# LPF.net
KiCad netlist of a schematic drawn in EAGLE
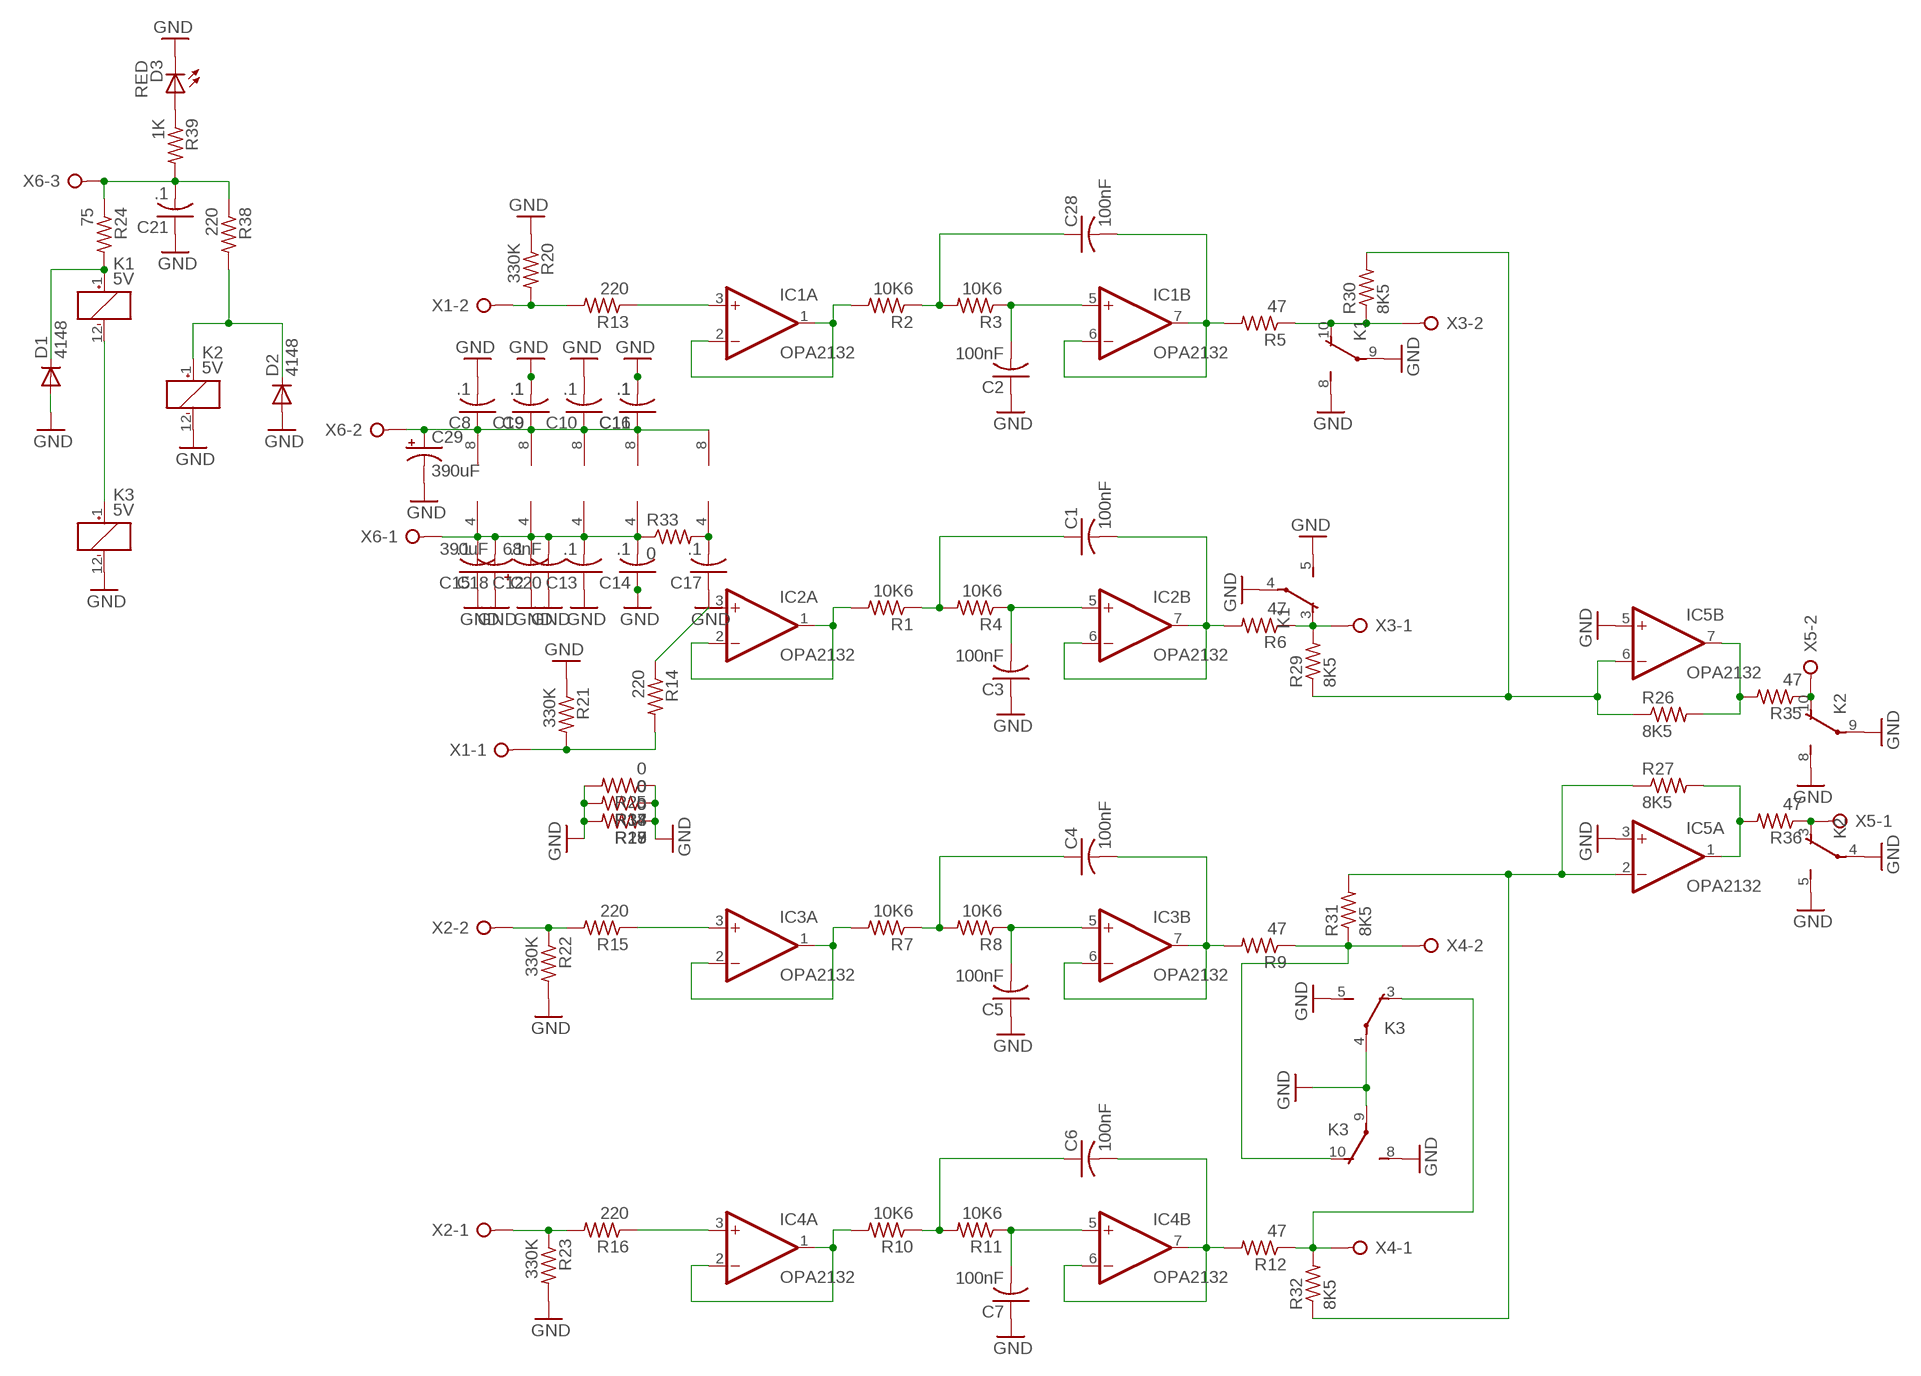
[diagram p0: schematic, sheet 1]

(export (version "E")
  (design (tool "Eeschema 10.0.6"))
  (components
    (comp (ref "C1")
      (value "100nF")
      (footprint "eagle-import:C050-075X075")
      (libsource (lib "eagle-import") (part "C-US050-075X075"))
    )
    (comp (ref "C2")
      (value "100nF")
      (footprint "eagle-import:C050-075X075")
      (libsource (lib "eagle-import") (part "C-US050-075X075"))
    )
    (comp (ref "C3")
      (value "100nF")
      (footprint "eagle-import:C050-075X075")
      (libsource (lib "eagle-import") (part "C-US050-075X075"))
    )
    (comp (ref "C4")
      (value "100nF")
      (footprint "eagle-import:C050-075X075")
      (libsource (lib "eagle-import") (part "C-US050-075X075"))
    )
    (comp (ref "C5")
      (value "100nF")
      (footprint "eagle-import:C050-075X075")
      (libsource (lib "eagle-import") (part "C-US050-075X075"))
    )
    (comp (ref "C6")
      (value "100nF")
      (footprint "eagle-import:C050-075X075")
      (libsource (lib "eagle-import") (part "C-US050-075X075"))
    )
    (comp (ref "C7")
      (value "100nF")
      (footprint "eagle-import:C050-075X075")
      (libsource (lib "eagle-import") (part "C-US050-075X075"))
    )
    (comp (ref "C8")
      (value ".1")
      (footprint "eagle-import:C4532")
      (libsource (lib "eagle-import") (part "C-USC4532"))
    )
    (comp (ref "C9")
      (value ".1")
      (footprint "eagle-import:C4532")
      (libsource (lib "eagle-import") (part "C-USC4532"))
    )
    (comp (ref "C10")
      (value ".1")
      (footprint "eagle-import:C4532")
      (libsource (lib "eagle-import") (part "C-USC4532"))
    )
    (comp (ref "C11")
      (value ".1")
      (footprint "eagle-import:C4532")
      (libsource (lib "eagle-import") (part "C-USC4532"))
    )
    (comp (ref "C12")
      (value ".1")
      (footprint "eagle-import:C4532")
      (libsource (lib "eagle-import") (part "C-USC4532"))
    )
    (comp (ref "C13")
      (value ".1")
      (footprint "eagle-import:C4532")
      (libsource (lib "eagle-import") (part "C-USC4532"))
    )
    (comp (ref "C14")
      (value ".1")
      (footprint "eagle-import:C4532")
      (libsource (lib "eagle-import") (part "C-USC4532"))
    )
    (comp (ref "C15")
      (value ".1")
      (footprint "eagle-import:C4532")
      (libsource (lib "eagle-import") (part "C-USC4532"))
    )
    (comp (ref "C16")
      (value ".1")
      (footprint "eagle-import:C4532")
      (libsource (lib "eagle-import") (part "C-USC4532"))
    )
    (comp (ref "C17")
      (value ".1")
      (footprint "eagle-import:C4532")
      (libsource (lib "eagle-import") (part "C-USC4532"))
    )
    (comp (ref "C18")
      (value "390uF")
      (footprint "eagle-import:E5-13")
      (libsource (lib "eagle-import") (part "CPOL-USE5-13"))
    )
    (comp (ref "C19")
      (value ".1")
      (footprint "eagle-import:C4532")
      (libsource (lib "eagle-import") (part "C-USC4532"))
    )
    (comp (ref "C20")
      (value "68nF")
      (footprint "eagle-import:C075-042X103")
      (libsource (lib "eagle-import") (part "C-US075-042X103"))
    )
    (comp (ref "C21")
      (value ".1")
      (footprint "eagle-import:C4532")
      (libsource (lib "eagle-import") (part "C-USC4532"))
    )
    (comp (ref "C28")
      (value "100nF")
      (footprint "eagle-import:C050-075X075")
      (libsource (lib "eagle-import") (part "C-US050-075X075"))
    )
    (comp (ref "C29")
      (value "390uF")
      (footprint "eagle-import:E5-13")
      (libsource (lib "eagle-import") (part "CPOL-USE5-13"))
    )
    (comp (ref "D1")
      (value "4148")
      (footprint "eagle-import:DO35-7")
      (libsource (lib "eagle-import") (part "1N4148DO35-7"))
    )
    (comp (ref "D2")
      (value "4148")
      (footprint "eagle-import:DO35-7")
      (libsource (lib "eagle-import") (part "1N4148DO35-7"))
    )
    (comp (ref "D3")
      (value "RED")
      (footprint "eagle-import:SFH482")
      (libsource (lib "eagle-import") (part "SFH482"))
    )
    (comp (ref "IC1")
      (value "OPA2132")
      (footprint "eagle-import:DIL08")
      (libsource (lib "eagle-import") (part "1458NLM"))
    )
    (comp (ref "IC2")
      (value "OPA2132")
      (footprint "eagle-import:DIL08")
      (libsource (lib "eagle-import") (part "1458NLM"))
    )
    (comp (ref "IC3")
      (value "OPA2132")
      (footprint "eagle-import:DIL08")
      (libsource (lib "eagle-import") (part "1458NLM"))
    )
    (comp (ref "IC4")
      (value "OPA2132")
      (footprint "eagle-import:DIL08")
      (libsource (lib "eagle-import") (part "1458NLM"))
    )
    (comp (ref "IC5")
      (value "OPA2132")
      (footprint "eagle-import:DIL08")
      (libsource (lib "eagle-import") (part "1458NLM"))
    )
    (comp (ref "K1")
      (value "5V")
      (footprint "eagle-import:TX2")
      (fields
        (field (name "MF") "AROMAT/ MATSUSHITA")
        (field (name "MPN") "TX2-12V")
        (field (name "MF_1") "AROMAT/ MATSUSHITA")
        (field (name "MPN_1") "TX2-12V")
        (field (name "OC_FARNELL") "1200952")
        (field (name "OC_NEWARK") "67K1295")
      )
      (libsource (lib "eagle-import") (part "TX2?-12V"))
    )
    (comp (ref "K2")
      (value "5V")
      (footprint "eagle-import:TX2")
      (fields
        (field (name "MF") "AROMAT/ MATSUSHITA")
        (field (name "MPN") "TX2-12V")
        (field (name "MF_1") "AROMAT/ MATSUSHITA")
        (field (name "MPN_1") "TX2-12V")
        (field (name "OC_FARNELL") "1200952")
        (field (name "OC_NEWARK") "67K1295")
      )
      (libsource (lib "eagle-import") (part "TX2?-12V"))
    )
    (comp (ref "K3")
      (value "5V")
      (footprint "eagle-import:TX2")
      (fields
        (field (name "MF") "AROMAT/ MATSUSHITA")
        (field (name "MPN") "TX2-12V")
        (field (name "MF_1") "AROMAT/ MATSUSHITA")
        (field (name "MPN_1") "TX2-12V")
        (field (name "OC_FARNELL") "1200952")
        (field (name "OC_NEWARK") "67K1295")
      )
      (libsource (lib "eagle-import") (part "TX2?-12V"))
    )
    (comp (ref "R1")
      (value "10K6")
      (footprint "eagle-import:0207_10")
      (libsource (lib "eagle-import") (part "R-US_0207/10"))
    )
    (comp (ref "R2")
      (value "10K6")
      (footprint "eagle-import:0207_10")
      (libsource (lib "eagle-import") (part "R-US_0207/10"))
    )
    (comp (ref "R3")
      (value "10K6")
      (footprint "eagle-import:0207_10")
      (libsource (lib "eagle-import") (part "R-US_0207/10"))
    )
    (comp (ref "R4")
      (value "10K6")
      (footprint "eagle-import:0207_10")
      (libsource (lib "eagle-import") (part "R-US_0207/10"))
    )
    (comp (ref "R5")
      (value "47")
      (footprint "eagle-import:0207_12")
      (libsource (lib "eagle-import") (part "R-US_0207/12"))
    )
    (comp (ref "R6")
      (value "47")
      (footprint "eagle-import:0207_12")
      (libsource (lib "eagle-import") (part "R-US_0207/12"))
    )
    (comp (ref "R7")
      (value "10K6")
      (footprint "eagle-import:0207_10")
      (libsource (lib "eagle-import") (part "R-US_0207/10"))
    )
    (comp (ref "R8")
      (value "10K6")
      (footprint "eagle-import:0207_10")
      (libsource (lib "eagle-import") (part "R-US_0207/10"))
    )
    (comp (ref "R9")
      (value "47")
      (footprint "eagle-import:0207_12")
      (libsource (lib "eagle-import") (part "R-US_0207/12"))
    )
    (comp (ref "R10")
      (value "10K6")
      (footprint "eagle-import:0207_10")
      (libsource (lib "eagle-import") (part "R-US_0207/10"))
    )
    (comp (ref "R11")
      (value "10K6")
      (footprint "eagle-import:0207_10")
      (libsource (lib "eagle-import") (part "R-US_0207/10"))
    )
    (comp (ref "R12")
      (value "47")
      (footprint "eagle-import:0207_10")
      (libsource (lib "eagle-import") (part "R-US_0207/10"))
    )
    (comp (ref "R13")
      (value "220")
      (footprint "eagle-import:0207_10")
      (libsource (lib "eagle-import") (part "R-US_0207/10"))
    )
    (comp (ref "R14")
      (value "220")
      (footprint "eagle-import:0207_10")
      (libsource (lib "eagle-import") (part "R-US_0207/10"))
    )
    (comp (ref "R15")
      (value "220")
      (footprint "eagle-import:0207_10")
      (libsource (lib "eagle-import") (part "R-US_0207/10"))
    )
    (comp (ref "R16")
      (value "220")
      (footprint "eagle-import:0207_10")
      (libsource (lib "eagle-import") (part "R-US_0207/10"))
    )
    (comp (ref "R17")
      (value "0")
      (footprint "eagle-import:0204_7")
      (libsource (lib "eagle-import") (part "R-US_0204/7"))
    )
    (comp (ref "R18")
      (value "0")
      (footprint "eagle-import:0204_7")
      (libsource (lib "eagle-import") (part "R-US_0204/7"))
    )
    (comp (ref "R19")
      (value "0")
      (footprint "eagle-import:0204_7")
      (libsource (lib "eagle-import") (part "R-US_0204/7"))
    )
    (comp (ref "R20")
      (value "330K")
      (footprint "eagle-import:R1210")
      (libsource (lib "eagle-import") (part "R-US_R1210"))
    )
    (comp (ref "R21")
      (value "330K")
      (footprint "eagle-import:R1210")
      (libsource (lib "eagle-import") (part "R-US_R1210"))
    )
    (comp (ref "R22")
      (value "330K")
      (footprint "eagle-import:R1210")
      (libsource (lib "eagle-import") (part "R-US_R1210"))
    )
    (comp (ref "R23")
      (value "330K")
      (footprint "eagle-import:R1210")
      (libsource (lib "eagle-import") (part "R-US_R1210"))
    )
    (comp (ref "R24")
      (value "75")
      (footprint "eagle-import:0207_10")
      (libsource (lib "eagle-import") (part "R-US_0207/10"))
    )
    (comp (ref "R25")
      (value "0")
      (footprint "eagle-import:0204_7")
      (libsource (lib "eagle-import") (part "R-US_0204/7"))
    )
    (comp (ref "R26")
      (value "8K5")
      (footprint "eagle-import:R1210")
      (libsource (lib "eagle-import") (part "R-US_R1210"))
    )
    (comp (ref "R27")
      (value "8K5")
      (footprint "eagle-import:R1210")
      (libsource (lib "eagle-import") (part "R-US_R1210"))
    )
    (comp (ref "R28")
      (value "0")
      (footprint "eagle-import:0204_7")
      (libsource (lib "eagle-import") (part "R-US_0204/7"))
    )
    (comp (ref "R29")
      (value "8K5")
      (footprint "eagle-import:R1210")
      (libsource (lib "eagle-import") (part "R-US_R1210"))
    )
    (comp (ref "R30")
      (value "8K5")
      (footprint "eagle-import:R1210")
      (libsource (lib "eagle-import") (part "R-US_R1210"))
    )
    (comp (ref "R31")
      (value "8K5")
      (footprint "eagle-import:R1210")
      (libsource (lib "eagle-import") (part "R-US_R1210"))
    )
    (comp (ref "R32")
      (value "8K5")
      (footprint "eagle-import:R1210")
      (libsource (lib "eagle-import") (part "R-US_R1210"))
    )
    (comp (ref "R33")
      (value "0")
      (footprint "eagle-import:0207_12")
      (libsource (lib "eagle-import") (part "R-US_0207/12"))
    )
    (comp (ref "R34")
      (value "0")
      (footprint "eagle-import:0204_7")
      (libsource (lib "eagle-import") (part "R-US_0204/7"))
    )
    (comp (ref "R35")
      (value "47")
      (footprint "eagle-import:0207_10")
      (libsource (lib "eagle-import") (part "R-US_0207/10"))
    )
    (comp (ref "R36")
      (value "47")
      (footprint "eagle-import:0207_10")
      (libsource (lib "eagle-import") (part "R-US_0207/10"))
    )
    (comp (ref "R37")
      (value "0")
      (footprint "eagle-import:0207_10")
      (libsource (lib "eagle-import") (part "R-US_0207/10"))
    )
    (comp (ref "R38")
      (value "220")
      (footprint "eagle-import:0309_12")
      (libsource (lib "eagle-import") (part "R-US_0309/12"))
    )
    (comp (ref "R39")
      (value "1K")
      (footprint "eagle-import:0207_10")
      (libsource (lib "eagle-import") (part "R-US_0207/10"))
    )
    (comp (ref "X1")
      (value "W237-02P")
      (footprint "eagle-import:W237-132")
      (libsource (lib "eagle-import") (part "W237-02P"))
    )
    (comp (ref "X2")
      (value "W237-02P")
      (footprint "eagle-import:W237-132")
      (libsource (lib "eagle-import") (part "W237-02P"))
    )
    (comp (ref "X3")
      (value "W237-02P")
      (footprint "eagle-import:W237-132")
      (fields (field (name "OC_FARNELL") "unknown") (field (name "OC_NEWARK") "unknown"))
      (libsource (lib "eagle-import") (part "W237-02P"))
    )
    (comp (ref "X4")
      (value "W237-02P")
      (footprint "eagle-import:W237-132")
      (fields (field (name "OC_FARNELL") "unknown") (field (name "OC_NEWARK") "unknown"))
      (libsource (lib "eagle-import") (part "W237-02P"))
    )
    (comp (ref "X5")
      (value "W237-02P")
      (footprint "eagle-import:W237-132")
      (fields (field (name "OC_FARNELL") "unknown") (field (name "OC_NEWARK") "unknown"))
      (libsource (lib "eagle-import") (part "W237-02P"))
    )
    (comp (ref "X6")
      (value "W237-3E")
      (footprint "eagle-import:W237-3E")
      (libsource (lib "eagle-import") (part "W237-3E"))
    )
  )
  (nets
    (net (code "1") (name "GND") (class "Default")
      (node (ref "C10") (pin "2") (pinfunction "2_2") (pintype "passive"))
      (node (ref "C11") (pin "2") (pinfunction "2_2") (pintype "passive"))
      (node (ref "C12") (pin "1") (pinfunction "1_1") (pintype "passive"))
      (node (ref "C13") (pin "1") (pinfunction "1_1") (pintype "passive"))
      (node (ref "C14") (pin "1") (pinfunction "1_1") (pintype "passive"))
      (node (ref "C15") (pin "1") (pinfunction "1_1") (pintype "passive"))
      (node (ref "C16") (pin "2") (pinfunction "2_2") (pintype "passive"))
      (node (ref "C17") (pin "1") (pinfunction "1_1") (pintype "passive"))
      (node (ref "C18") (pin "+") (pinfunction "+_+") (pintype "passive"))
      (node (ref "C19") (pin "2") (pinfunction "2_2") (pintype "passive"))
      (node (ref "C2") (pin "1") (pinfunction "1_1") (pintype "passive"))
      (node (ref "C20") (pin "1") (pinfunction "1_1") (pintype "passive"))
      (node (ref "C21") (pin "1") (pinfunction "1_1") (pintype "passive"))
      (node (ref "C29") (pin "-") (pinfunction "-_-") (pintype "passive"))
      (node (ref "C3") (pin "1") (pinfunction "1_1") (pintype "passive"))
      (node (ref "C5") (pin "1") (pinfunction "1_1") (pintype "passive"))
      (node (ref "C7") (pin "1") (pinfunction "1_1") (pintype "passive"))
      (node (ref "C8") (pin "2") (pinfunction "2_2") (pintype "passive"))
      (node (ref "C9") (pin "2") (pinfunction "2_2") (pintype "passive"))
      (node (ref "D1") (pin "A") (pinfunction "A_A") (pintype "passive"))
      (node (ref "D2") (pin "A") (pinfunction "A_A") (pintype "passive"))
      (node (ref "D3") (pin "K") (pinfunction "C_K") (pintype "passive"))
      (node (ref "IC5") (pin "3") (pinfunction "+IN_3") (pintype "input"))
      (node (ref "IC5") (pin "5") (pinfunction "+IN_5") (pintype "input"))
      (node (ref "K1") (pin "4") (pinfunction "P_4") (pintype "passive"))
      (node (ref "K1") (pin "5") (pinfunction "S_5") (pintype "passive"))
      (node (ref "K1") (pin "8") (pinfunction "S_8") (pintype "passive"))
      (node (ref "K1") (pin "9") (pinfunction "P_9") (pintype "passive"))
      (node (ref "K2") (pin "12") (pinfunction "-_12") (pintype "passive"))
      (node (ref "K2") (pin "4") (pinfunction "P_4") (pintype "passive"))
      (node (ref "K2") (pin "5") (pinfunction "S_5") (pintype "passive"))
      (node (ref "K2") (pin "8") (pinfunction "S_8") (pintype "passive"))
      (node (ref "K2") (pin "9") (pinfunction "P_9") (pintype "passive"))
      (node (ref "K3") (pin "12") (pinfunction "-_12") (pintype "passive"))
      (node (ref "K3") (pin "4") (pinfunction "P_4") (pintype "passive"))
      (node (ref "K3") (pin "5") (pinfunction "S_5") (pintype "passive"))
      (node (ref "K3") (pin "8") (pinfunction "S_8") (pintype "passive"))
      (node (ref "K3") (pin "9") (pinfunction "P_9") (pintype "passive"))
      (node (ref "R17") (pin "1") (pinfunction "1_1") (pintype "passive"))
      (node (ref "R17") (pin "2") (pinfunction "2_2") (pintype "passive"))
      (node (ref "R18") (pin "1") (pinfunction "1_1") (pintype "passive"))
      (node (ref "R18") (pin "2") (pinfunction "2_2") (pintype "passive"))
      (node (ref "R19") (pin "1") (pinfunction "1_1") (pintype "passive"))
      (node (ref "R19") (pin "2") (pinfunction "2_2") (pintype "passive"))
      (node (ref "R20") (pin "1") (pinfunction "1_1") (pintype "passive"))
      (node (ref "R21") (pin "1") (pinfunction "1_1") (pintype "passive"))
      (node (ref "R22") (pin "2") (pinfunction "2_2") (pintype "passive"))
      (node (ref "R23") (pin "2") (pinfunction "2_2") (pintype "passive"))
      (node (ref "R25") (pin "1") (pinfunction "1_1") (pintype "passive"))
      (node (ref "R25") (pin "2") (pinfunction "2_2") (pintype "passive"))
      (node (ref "R28") (pin "1") (pinfunction "1_1") (pintype "passive"))
      (node (ref "R28") (pin "2") (pinfunction "2_2") (pintype "passive"))
      (node (ref "R34") (pin "1") (pinfunction "1_1") (pintype "passive"))
      (node (ref "R34") (pin "2") (pinfunction "2_2") (pintype "passive"))
      (node (ref "R37") (pin "1") (pinfunction "1_1") (pintype "passive"))
      (node (ref "R37") (pin "2") (pinfunction "2_2") (pintype "passive"))
    )
    (net (code "2") (name "Net-(C1-Pad1)") (class "Default")
      (node (ref "C1") (pin "1") (pinfunction "1_1") (pintype "passive"))
      (node (ref "R1") (pin "1") (pinfunction "1_1") (pintype "passive"))
      (node (ref "R4") (pin "2") (pinfunction "2_2") (pintype "passive"))
    )
    (net (code "3") (name "Net-(C4-Pad1)") (class "Default")
      (node (ref "C4") (pin "1") (pinfunction "1_1") (pintype "passive"))
      (node (ref "R7") (pin "1") (pinfunction "1_1") (pintype "passive"))
      (node (ref "R8") (pin "2") (pinfunction "2_2") (pintype "passive"))
    )
    (net (code "4") (name "Net-(C6-Pad1)") (class "Default")
      (node (ref "C6") (pin "1") (pinfunction "1_1") (pintype "passive"))
      (node (ref "R10") (pin "1") (pinfunction "1_1") (pintype "passive"))
      (node (ref "R11") (pin "2") (pinfunction "2_2") (pintype "passive"))
    )
    (net (code "5") (name "Net-(C28-Pad1)") (class "Default")
      (node (ref "C28") (pin "1") (pinfunction "1_1") (pintype "passive"))
      (node (ref "R2") (pin "1") (pinfunction "1_1") (pintype "passive"))
      (node (ref "R3") (pin "2") (pinfunction "2_2") (pintype "passive"))
    )
    (net (code "6") (name "Net-(D3-PadA)") (class "Default")
      (node (ref "D3") (pin "A") (pinfunction "A_A") (pintype "passive"))
      (node (ref "R39") (pin "1") (pinfunction "1_1") (pintype "passive"))
    )
    (net (code "7") (name "Net-(IC1A-+IN)") (class "Default")
      (node (ref "IC1") (pin "3") (pinfunction "+IN_3") (pintype "input"))
      (node (ref "R13") (pin "1") (pinfunction "1_1") (pintype "passive"))
    )
    (net (code "8") (name "Net-(IC1A--IN)") (class "Default")
      (node (ref "IC1") (pin "1") (pinfunction "OUT_1") (pintype "output"))
      (node (ref "IC1") (pin "2") (pinfunction "-IN_2") (pintype "input"))
      (node (ref "R2") (pin "2") (pinfunction "2_2") (pintype "passive"))
    )
    (net (code "9") (name "Net-(IC1B-+IN)") (class "Default")
      (node (ref "C2") (pin "2") (pinfunction "2_2") (pintype "passive"))
      (node (ref "IC1") (pin "5") (pinfunction "+IN_5") (pintype "input"))
      (node (ref "R3") (pin "1") (pinfunction "1_1") (pintype "passive"))
    )
    (net (code "10") (name "Net-(IC1B--IN)") (class "Default")
      (node (ref "C28") (pin "2") (pinfunction "2_2") (pintype "passive"))
      (node (ref "IC1") (pin "6") (pinfunction "-IN_6") (pintype "input"))
      (node (ref "IC1") (pin "7") (pinfunction "OUT_7") (pintype "output"))
      (node (ref "R5") (pin "2") (pinfunction "2_2") (pintype "passive"))
    )
    (net (code "11") (name "Net-(IC1C-V+)") (class "Default")
      (node (ref "C10") (pin "1") (pinfunction "1_1") (pintype "passive"))
      (node (ref "C11") (pin "1") (pinfunction "1_1") (pintype "passive"))
      (node (ref "C16") (pin "1") (pinfunction "1_1") (pintype "passive"))
      (node (ref "C19") (pin "1") (pinfunction "1_1") (pintype "passive"))
      (node (ref "C29") (pin "+") (pinfunction "+_+") (pintype "passive"))
      (node (ref "C8") (pin "1") (pinfunction "1_1") (pintype "passive"))
      (node (ref "C9") (pin "1") (pinfunction "1_1") (pintype "passive"))
      (node (ref "IC1") (pin "8") (pinfunction "V+_8") (pintype "power_in"))
      (node (ref "IC2") (pin "8") (pinfunction "V+_8") (pintype "power_in"))
      (node (ref "IC3") (pin "8") (pinfunction "V+_8") (pintype "power_in"))
      (node (ref "IC4") (pin "8") (pinfunction "V+_8") (pintype "power_in"))
      (node (ref "IC5") (pin "8") (pinfunction "V+_8") (pintype "power_in"))
      (node (ref "X6") (pin "2") (pinfunction "KL_2") (pintype "passive"))
    )
    (net (code "12") (name "Net-(IC1C-V-)") (class "Default")
      (node (ref "C12") (pin "2") (pinfunction "2_2") (pintype "passive"))
      (node (ref "C13") (pin "2") (pinfunction "2_2") (pintype "passive"))
      (node (ref "C14") (pin "2") (pinfunction "2_2") (pintype "passive"))
      (node (ref "C15") (pin "2") (pinfunction "2_2") (pintype "passive"))
      (node (ref "C18") (pin "-") (pinfunction "-_-") (pintype "passive"))
      (node (ref "C20") (pin "2") (pinfunction "2_2") (pintype "passive"))
      (node (ref "IC1") (pin "4") (pinfunction "V-_4") (pintype "power_in"))
      (node (ref "IC2") (pin "4") (pinfunction "V-_4") (pintype "power_in"))
      (node (ref "IC3") (pin "4") (pinfunction "V-_4") (pintype "power_in"))
      (node (ref "IC4") (pin "4") (pinfunction "V-_4") (pintype "power_in"))
      (node (ref "R33") (pin "1") (pinfunction "1_1") (pintype "passive"))
      (node (ref "X6") (pin "1") (pinfunction "KL_1") (pintype "passive"))
    )
    (net (code "13") (name "Net-(IC2A-+IN)") (class "Default")
      (node (ref "IC2") (pin "3") (pinfunction "+IN_3") (pintype "input"))
      (node (ref "R14") (pin "1") (pinfunction "1_1") (pintype "passive"))
    )
    (net (code "14") (name "Net-(IC2A--IN)") (class "Default")
      (node (ref "IC2") (pin "1") (pinfunction "OUT_1") (pintype "output"))
      (node (ref "IC2") (pin "2") (pinfunction "-IN_2") (pintype "input"))
      (node (ref "R1") (pin "2") (pinfunction "2_2") (pintype "passive"))
    )
    (net (code "15") (name "Net-(IC2B-+IN)") (class "Default")
      (node (ref "C3") (pin "2") (pinfunction "2_2") (pintype "passive"))
      (node (ref "IC2") (pin "5") (pinfunction "+IN_5") (pintype "input"))
      (node (ref "R4") (pin "1") (pinfunction "1_1") (pintype "passive"))
    )
    (net (code "16") (name "Net-(IC2B--IN)") (class "Default")
      (node (ref "C1") (pin "2") (pinfunction "2_2") (pintype "passive"))
      (node (ref "IC2") (pin "6") (pinfunction "-IN_6") (pintype "input"))
      (node (ref "IC2") (pin "7") (pinfunction "OUT_7") (pintype "output"))
      (node (ref "R6") (pin "2") (pinfunction "2_2") (pintype "passive"))
    )
    (net (code "17") (name "Net-(IC3A-+IN)") (class "Default")
      (node (ref "IC3") (pin "3") (pinfunction "+IN_3") (pintype "input"))
      (node (ref "R15") (pin "1") (pinfunction "1_1") (pintype "passive"))
    )
    (net (code "18") (name "Net-(IC3A--IN)") (class "Default")
      (node (ref "IC3") (pin "1") (pinfunction "OUT_1") (pintype "output"))
      (node (ref "IC3") (pin "2") (pinfunction "-IN_2") (pintype "input"))
      (node (ref "R7") (pin "2") (pinfunction "2_2") (pintype "passive"))
    )
    (net (code "19") (name "Net-(IC3B-+IN)") (class "Default")
      (node (ref "C5") (pin "2") (pinfunction "2_2") (pintype "passive"))
      (node (ref "IC3") (pin "5") (pinfunction "+IN_5") (pintype "input"))
      (node (ref "R8") (pin "1") (pinfunction "1_1") (pintype "passive"))
    )
    (net (code "20") (name "Net-(IC3B--IN)") (class "Default")
      (node (ref "C4") (pin "2") (pinfunction "2_2") (pintype "passive"))
      (node (ref "IC3") (pin "6") (pinfunction "-IN_6") (pintype "input"))
      (node (ref "IC3") (pin "7") (pinfunction "OUT_7") (pintype "output"))
      (node (ref "R9") (pin "2") (pinfunction "2_2") (pintype "passive"))
    )
    (net (code "21") (name "Net-(IC4A-+IN)") (class "Default")
      (node (ref "IC4") (pin "3") (pinfunction "+IN_3") (pintype "input"))
      (node (ref "R16") (pin "1") (pinfunction "1_1") (pintype "passive"))
    )
    (net (code "22") (name "Net-(IC4A--IN)") (class "Default")
      (node (ref "IC4") (pin "1") (pinfunction "OUT_1") (pintype "output"))
      (node (ref "IC4") (pin "2") (pinfunction "-IN_2") (pintype "input"))
      (node (ref "R10") (pin "2") (pinfunction "2_2") (pintype "passive"))
    )
    (net (code "23") (name "Net-(IC4B-+IN)") (class "Default")
      (node (ref "C7") (pin "2") (pinfunction "2_2") (pintype "passive"))
      (node (ref "IC4") (pin "5") (pinfunction "+IN_5") (pintype "input"))
      (node (ref "R11") (pin "1") (pinfunction "1_1") (pintype "passive"))
    )
    (net (code "24") (name "Net-(IC4B--IN)") (class "Default")
      (node (ref "C6") (pin "2") (pinfunction "2_2") (pintype "passive"))
      (node (ref "IC4") (pin "6") (pinfunction "-IN_6") (pintype "input"))
      (node (ref "IC4") (pin "7") (pinfunction "OUT_7") (pintype "output"))
      (node (ref "R12") (pin "2") (pinfunction "2_2") (pintype "passive"))
    )
    (net (code "25") (name "Net-(IC5A--IN)") (class "Default")
      (node (ref "IC5") (pin "2") (pinfunction "-IN_2") (pintype "input"))
      (node (ref "R27") (pin "1") (pinfunction "1_1") (pintype "passive"))
      (node (ref "R31") (pin "2") (pinfunction "2_2") (pintype "passive"))
      (node (ref "R32") (pin "1") (pinfunction "1_1") (pintype "passive"))
    )
    (net (code "26") (name "Net-(IC5A-OUT)") (class "Default")
      (node (ref "IC5") (pin "1") (pinfunction "OUT_1") (pintype "output"))
      (node (ref "R27") (pin "2") (pinfunction "2_2") (pintype "passive"))
      (node (ref "R36") (pin "2") (pinfunction "2_2") (pintype "passive"))
    )
    (net (code "27") (name "Net-(IC5B--IN)") (class "Default")
      (node (ref "IC5") (pin "6") (pinfunction "-IN_6") (pintype "input"))
      (node (ref "R26") (pin "1") (pinfunction "1_1") (pintype "passive"))
      (node (ref "R29") (pin "1") (pinfunction "1_1") (pintype "passive"))
      (node (ref "R30") (pin "2") (pinfunction "2_2") (pintype "passive"))
    )
    (net (code "28") (name "Net-(IC5B-OUT)") (class "Default")
      (node (ref "IC5") (pin "7") (pinfunction "OUT_7") (pintype "output"))
      (node (ref "R26") (pin "2") (pinfunction "2_2") (pintype "passive"))
      (node (ref "R35") (pin "2") (pinfunction "2_2") (pintype "passive"))
    )
    (net (code "29") (name "Net-(IC5C-V-)") (class "Default")
      (node (ref "C17") (pin "2") (pinfunction "2_2") (pintype "passive"))
      (node (ref "IC5") (pin "4") (pinfunction "V-_4") (pintype "power_in"))
      (node (ref "R33") (pin "2") (pinfunction "2_2") (pintype "passive"))
    )
    (net (code "30") (name "Net-(K1A-O)") (class "Default")
      (node (ref "K1") (pin "3") (pinfunction "O_3") (pintype "passive"))
      (node (ref "R29") (pin "2") (pinfunction "2_2") (pintype "passive"))
      (node (ref "R6") (pin "1") (pinfunction "1_1") (pintype "passive"))
      (node (ref "X3") (pin "1") (pinfunction "KL_1") (pintype "passive"))
    )
    (net (code "31") (name "Net-(K1B-O)") (class "Default")
      (node (ref "K1") (pin "10") (pinfunction "O_10") (pintype "passive"))
      (node (ref "R30") (pin "1") (pinfunction "1_1") (pintype "passive"))
      (node (ref "R5") (pin "1") (pinfunction "1_1") (pintype "passive"))
      (node (ref "X3") (pin "2") (pinfunction "KL_2") (pintype "passive"))
    )
    (net (code "32") (name "Net-(K1C-+)") (class "Default")
      (node (ref "D1") (pin "C") (pinfunction "C_C") (pintype "passive"))
      (node (ref "K1") (pin "1") (pinfunction "+_1") (pintype "passive"))
      (node (ref "R24") (pin "2") (pinfunction "2_2") (pintype "passive"))
    )
    (net (code "33") (name "Net-(K1C--)") (class "Default")
      (node (ref "K1") (pin "12") (pinfunction "-_12") (pintype "passive"))
      (node (ref "K3") (pin "1") (pinfunction "+_1") (pintype "passive"))
    )
    (net (code "34") (name "Net-(K2A-O)") (class "Default")
      (node (ref "K2") (pin "3") (pinfunction "O_3") (pintype "passive"))
      (node (ref "R36") (pin "1") (pinfunction "1_1") (pintype "passive"))
      (node (ref "X5") (pin "1") (pinfunction "KL_1") (pintype "passive"))
    )
    (net (code "35") (name "Net-(K2B-O)") (class "Default")
      (node (ref "K2") (pin "10") (pinfunction "O_10") (pintype "passive"))
      (node (ref "R35") (pin "1") (pinfunction "1_1") (pintype "passive"))
      (node (ref "X5") (pin "2") (pinfunction "KL_2") (pintype "passive"))
    )
    (net (code "36") (name "Net-(K2C-+)") (class "Default")
      (node (ref "D2") (pin "C") (pinfunction "C_C") (pintype "passive"))
      (node (ref "K2") (pin "1") (pinfunction "+_1") (pintype "passive"))
      (node (ref "R38") (pin "2") (pinfunction "2_2") (pintype "passive"))
    )
    (net (code "37") (name "Net-(K3A-O)") (class "Default")
      (node (ref "K3") (pin "3") (pinfunction "O_3") (pintype "passive"))
      (node (ref "R12") (pin "1") (pinfunction "1_1") (pintype "passive"))
      (node (ref "R32") (pin "2") (pinfunction "2_2") (pintype "passive"))
      (node (ref "X4") (pin "1") (pinfunction "KL_1") (pintype "passive"))
    )
    (net (code "38") (name "Net-(K3B-O)") (class "Default")
      (node (ref "K3") (pin "10") (pinfunction "O_10") (pintype "passive"))
      (node (ref "R31") (pin "1") (pinfunction "1_1") (pintype "passive"))
      (node (ref "R9") (pin "1") (pinfunction "1_1") (pintype "passive"))
      (node (ref "X4") (pin "2") (pinfunction "KL_2") (pintype "passive"))
    )
    (net (code "39") (name "Net-(X1A-KL)") (class "Default")
      (node (ref "R14") (pin "2") (pinfunction "2_2") (pintype "passive"))
      (node (ref "R21") (pin "2") (pinfunction "2_2") (pintype "passive"))
      (node (ref "X1") (pin "1") (pinfunction "KL_1") (pintype "passive"))
    )
    (net (code "40") (name "Net-(X1B-KL)") (class "Default")
      (node (ref "R13") (pin "2") (pinfunction "2_2") (pintype "passive"))
      (node (ref "R20") (pin "2") (pinfunction "2_2") (pintype "passive"))
      (node (ref "X1") (pin "2") (pinfunction "KL_2") (pintype "passive"))
    )
    (net (code "41") (name "Net-(X2A-KL)") (class "Default")
      (node (ref "R16") (pin "2") (pinfunction "2_2") (pintype "passive"))
      (node (ref "R23") (pin "1") (pinfunction "1_1") (pintype "passive"))
      (node (ref "X2") (pin "1") (pinfunction "KL_1") (pintype "passive"))
    )
    (net (code "42") (name "Net-(X2B-KL)") (class "Default")
      (node (ref "R15") (pin "2") (pinfunction "2_2") (pintype "passive"))
      (node (ref "R22") (pin "1") (pinfunction "1_1") (pintype "passive"))
      (node (ref "X2") (pin "2") (pinfunction "KL_2") (pintype "passive"))
    )
    (net (code "43") (name "Net-(X6C-KL)") (class "Default")
      (node (ref "C21") (pin "2") (pinfunction "2_2") (pintype "passive"))
      (node (ref "R24") (pin "1") (pinfunction "1_1") (pintype "passive"))
      (node (ref "R38") (pin "1") (pinfunction "1_1") (pintype "passive"))
      (node (ref "R39") (pin "2") (pinfunction "2_2") (pintype "passive"))
      (node (ref "X6") (pin "3") (pinfunction "KL_3") (pintype "passive"))
    )
  )
)
